# 8_imu_debug_conn.net
KiCad netlist of a schematic drawn in Altium Designer
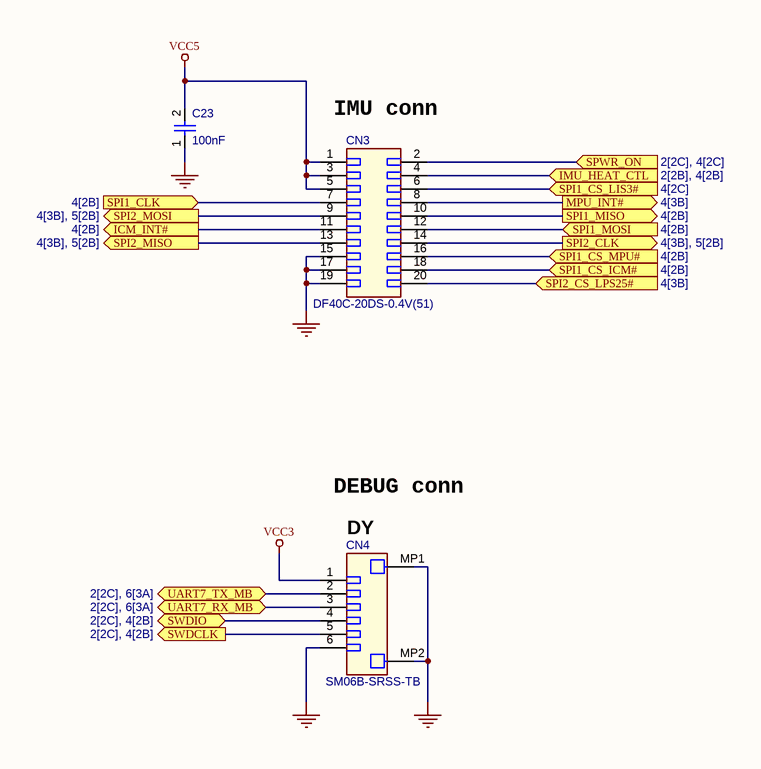
[diagram p0: 8_imu&debug_conn.SchDoc]

(export (version "E")
  (design (tool "Eeschema 10.0.6"))
  (components
    (comp (ref "C23")
      (value "100nF")
      (footprint "CAPC0402(1005)60_L")
      (description "Chip Capacitor, 100nF +/-20%, 10V, 0402, Thickness 0.6 mm")
      (fields (field (name "TOLERANCE") "20%") (field (name "MANUFACTURER") "KEMET"))
      (libsource (lib "Kame_FMU") (part "Capacitor 100nF +/-20% 10V 0402"))
    )
    (comp (ref "CN3")
      (value "DF40C-20DS-0.4V(51)")
      (footprint "HIRO-DF40C-20DS-0.4V(51)_V")
      (description "Receptacle Connector, 30 V, 0.3 A, -35 to 85 degC, RoHS, Tape and Reel")
      (fields (field (name "MANUFACTURER") "Hirose"))
      (libsource (lib "Kame_FMU") (part "DF40C-20DS-0.4V(51)"))
    )
    (comp (ref "CN4")
      (value "SM06B-SRSS-TB")
      (footprint "JST-SM06B-SRSS-TB_V")
      (description "Male Header, Pitch 1 mm, 1 x 6 Position, Height 2.95 mm, -25 to 85 degC, RoHS, Tape and Reel")
      (fields
        (field (name "MANUFACTURER") "JST")
        (field (name "MANUFACTURER PART NUMBER") "SM06B-SRSS-TB(LF)(SN)")
      )
      (libsource (lib "Kame_FMU") (part "SM06B-SRSS-TB"))
    )
  )
  (nets
    (net (code "1") (name "/ICM_INT#") (class "Default")
      (node (ref "CN3") (pin "11") (pinfunction "11_11") (pintype "passive"))
    )
    (net (code "2") (name "/IMU_HEAT_CTL") (class "Default")
      (node (ref "CN3") (pin "4") (pinfunction "4_4") (pintype "passive"))
    )
    (net (code "3") (name "/MPU_INT#") (class "Default")
      (node (ref "CN3") (pin "8") (pinfunction "8_8") (pintype "passive"))
    )
    (net (code "4") (name "/SPI1_CLK") (class "Default")
      (node (ref "CN3") (pin "7") (pinfunction "7_7") (pintype "passive"))
    )
    (net (code "5") (name "/SPI1_CS_ICM#") (class "Default")
      (node (ref "CN3") (pin "18") (pinfunction "18_18") (pintype "passive"))
    )
    (net (code "6") (name "/SPI1_CS_LIS3#") (class "Default")
      (node (ref "CN3") (pin "6") (pinfunction "6_6") (pintype "passive"))
    )
    (net (code "7") (name "/SPI1_CS_MPU#") (class "Default")
      (node (ref "CN3") (pin "16") (pinfunction "16_16") (pintype "passive"))
    )
    (net (code "8") (name "/SPI1_MISO") (class "Default")
      (node (ref "CN3") (pin "10") (pinfunction "10_10") (pintype "passive"))
    )
    (net (code "9") (name "/SPI1_MOSI") (class "Default")
      (node (ref "CN3") (pin "12") (pinfunction "12_12") (pintype "passive"))
    )
    (net (code "10") (name "/SPI2_CLK") (class "Default")
      (node (ref "CN3") (pin "14") (pinfunction "14_14") (pintype "passive"))
    )
    (net (code "11") (name "/SPI2_CS_LPS25#") (class "Default")
      (node (ref "CN3") (pin "20") (pinfunction "20_20") (pintype "passive"))
    )
    (net (code "12") (name "/SPI2_MISO") (class "Default")
      (node (ref "CN3") (pin "13") (pinfunction "13_13") (pintype "passive"))
    )
    (net (code "13") (name "/SPI2_MOSI") (class "Default")
      (node (ref "CN3") (pin "9") (pinfunction "9_9") (pintype "passive"))
    )
    (net (code "14") (name "/SPWR_ON") (class "Default")
      (node (ref "CN3") (pin "2") (pinfunction "2_2") (pintype "passive"))
    )
    (net (code "15") (name "/SWDCLK") (class "Default")
      (node (ref "CN4") (pin "5") (pinfunction "5_5") (pintype "passive"))
    )
    (net (code "16") (name "/SWDIO") (class "Default")
      (node (ref "CN4") (pin "4") (pinfunction "4_4") (pintype "passive"))
    )
    (net (code "17") (name "/UART7_RX_MB") (class "Default")
      (node (ref "CN4") (pin "3") (pinfunction "3_3") (pintype "passive"))
    )
    (net (code "18") (name "/UART7_TX_MB") (class "Default")
      (node (ref "CN4") (pin "2") (pinfunction "2_2") (pintype "passive"))
    )
    (net (code "19") (name "GND") (class "Default")
      (node (ref "C23") (pin "1") (pinfunction "1_1") (pintype "passive"))
      (node (ref "CN3") (pin "15") (pinfunction "15_15") (pintype "passive"))
      (node (ref "CN3") (pin "17") (pinfunction "17_17") (pintype "passive"))
      (node (ref "CN3") (pin "19") (pinfunction "19_19") (pintype "passive"))
      (node (ref "CN4") (pin "6") (pinfunction "6_6") (pintype "passive"))
      (node (ref "CN4") (pin "MP1") (pinfunction "MP1_MP1") (pintype "passive"))
      (node (ref "CN4") (pin "MP2") (pinfunction "MP2_MP2") (pintype "passive"))
    )
    (net (code "20") (name "VCC3") (class "Default")
      (node (ref "CN4") (pin "1") (pinfunction "1_1") (pintype "passive"))
    )
    (net (code "21") (name "VCC5") (class "Default")
      (node (ref "C23") (pin "2") (pinfunction "2_2") (pintype "passive"))
      (node (ref "CN3") (pin "1") (pinfunction "1_1") (pintype "passive"))
      (node (ref "CN3") (pin "3") (pinfunction "3_3") (pintype "passive"))
      (node (ref "CN3") (pin "5") (pinfunction "5_5") (pintype "passive"))
    )
  )
)
